# long-3_3v.net
KiCad netlist of a schematic drawn in EAGLE
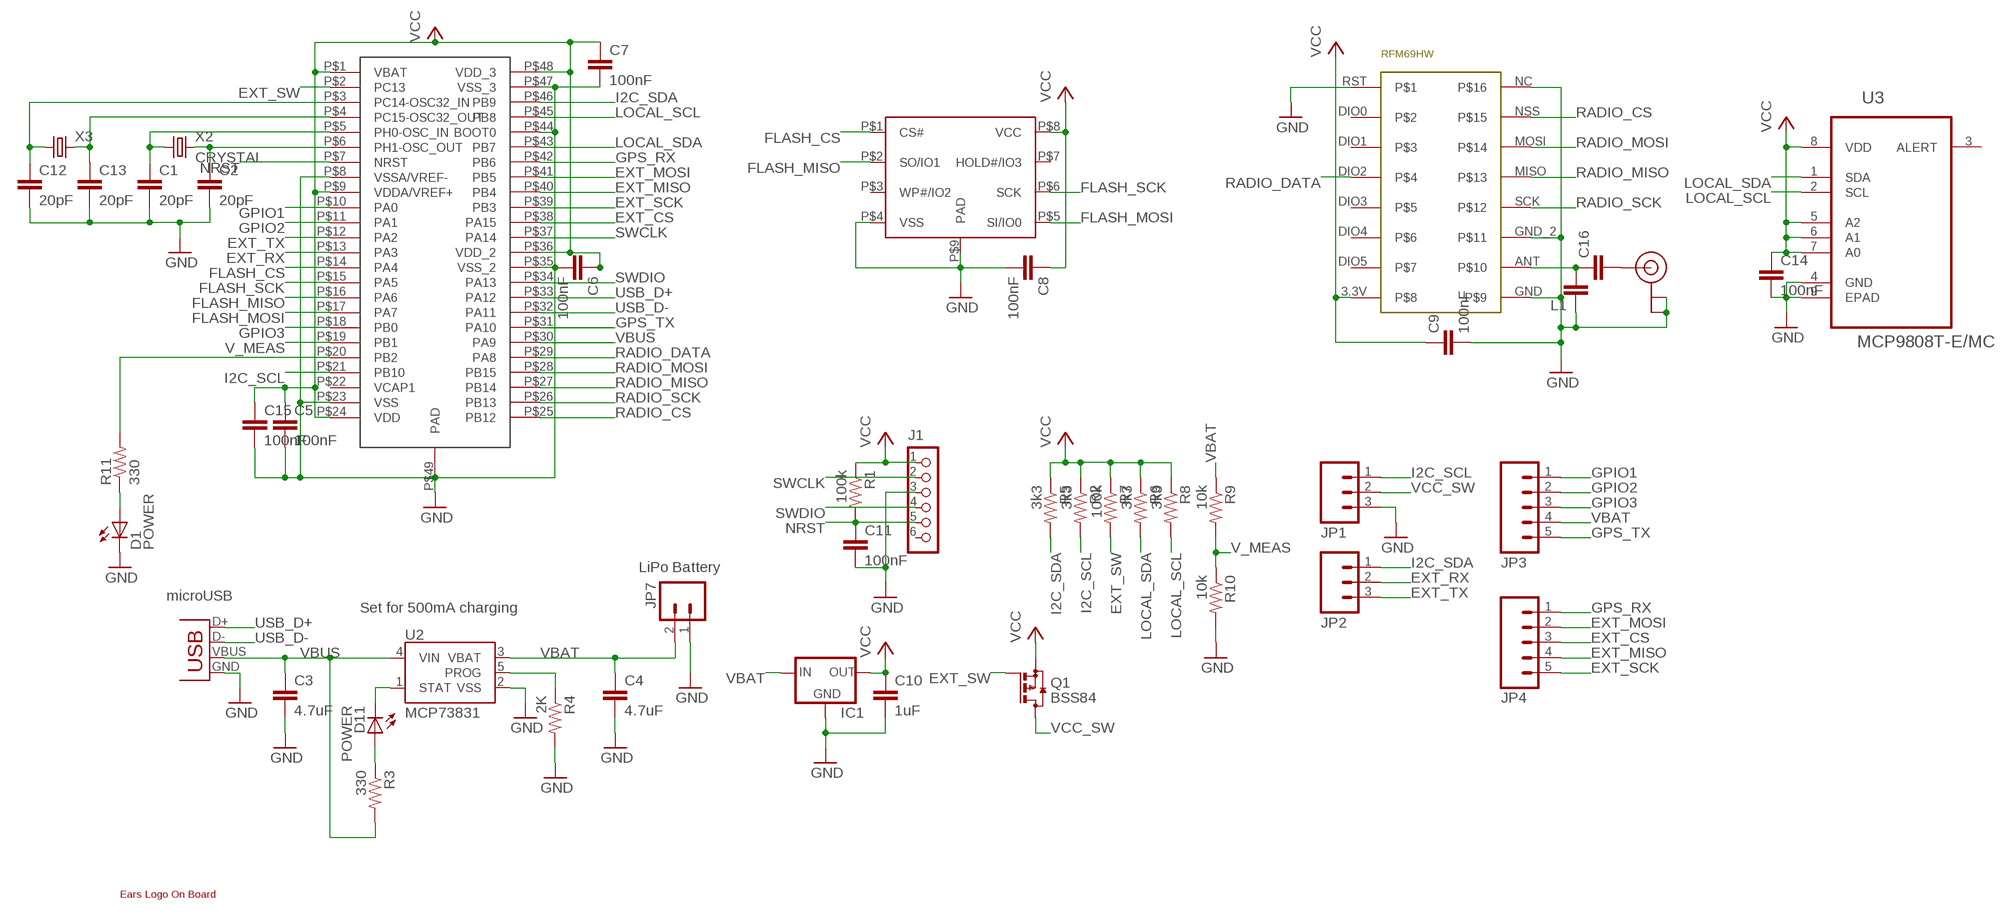
[diagram p0: schematic, sheet 1]

(export (version "E")
  (design (tool "Eeschema 10.0.6"))
  (components
    (comp (ref "C1")
      (value "20pF")
      (footprint "eagle-import:C0402")
      (libsource (lib "eagle-import") (part "C-EUC0402"))
    )
    (comp (ref "C2")
      (value "20pF")
      (footprint "eagle-import:C0402")
      (libsource (lib "eagle-import") (part "C-EUC0402"))
    )
    (comp (ref "C3")
      (value "4.7uF")
      (footprint "eagle-import:0402-CAP")
      (libsource (lib "eagle-import") (part "CAP0402-CAP"))
    )
    (comp (ref "C4")
      (value "4.7uF")
      (footprint "eagle-import:0402-CAP")
      (libsource (lib "eagle-import") (part "CAP0402-CAP"))
    )
    (comp (ref "C5")
      (value "100nF")
      (footprint "eagle-import:C0402")
      (libsource (lib "eagle-import") (part "C-EUC0402"))
    )
    (comp (ref "C6")
      (value "100nF")
      (footprint "eagle-import:C0402")
      (libsource (lib "eagle-import") (part "C-EUC0402"))
    )
    (comp (ref "C7")
      (value "100nF")
      (footprint "eagle-import:C0402")
      (libsource (lib "eagle-import") (part "C-EUC0402"))
    )
    (comp (ref "C8")
      (value "100nF")
      (footprint "eagle-import:C0402")
      (libsource (lib "eagle-import") (part "C-EUC0402"))
    )
    (comp (ref "C9")
      (value "100nF")
      (footprint "eagle-import:C0402")
      (libsource (lib "eagle-import") (part "C-EUC0402"))
    )
    (comp (ref "C10")
      (value "1uF")
      (footprint "eagle-import:C0402")
      (libsource (lib "eagle-import") (part "C-EUC0402"))
    )
    (comp (ref "C11")
      (value "100nF")
      (footprint "eagle-import:C0402")
      (libsource (lib "eagle-import") (part "C-EUC0402"))
    )
    (comp (ref "C12")
      (value "20pF")
      (footprint "eagle-import:C0402")
      (libsource (lib "eagle-import") (part "C-EUC0402"))
    )
    (comp (ref "C13")
      (value "20pF")
      (footprint "eagle-import:C0402")
      (libsource (lib "eagle-import") (part "C-EUC0402"))
    )
    (comp (ref "C14")
      (value "100nF")
      (footprint "eagle-import:C0402")
      (libsource (lib "eagle-import") (part "C-EUC0402"))
    )
    (comp (ref "C15")
      (value "100nF")
      (footprint "eagle-import:C0402")
      (libsource (lib "eagle-import") (part "C-EUC0402"))
    )
    (comp (ref "C16")
      (value "C-EUC0402")
      (footprint "eagle-import:C0402")
      (libsource (lib "eagle-import") (part "C-EUC0402"))
    )
    (comp (ref "D1")
      (value "POWER")
      (footprint "eagle-import:LED-0603")
      (libsource (lib "eagle-import") (part "LED0603"))
    )
    (comp (ref "D11")
      (value "POWER")
      (footprint "eagle-import:LED-0603")
      (libsource (lib "eagle-import") (part "LED0603"))
    )
    (comp (ref "IC1")
      (value "XC63FPM")
      (footprint "eagle-import:SOT23")
      (libsource (lib "eagle-import") (part "XC63FPM"))
    )
    (comp (ref "J1")
      (value "CON_HEADER_1X06-SMD-RIGHT-ANGLED")
      (footprint "eagle-import:M1X6_MALE_RIGHT_ANGLED_SMD")
      (libsource (lib "eagle-import") (part "CON_HEADER_1X06-SMD-RIGHT-ANGLED"))
    )
    (comp (ref "JP1")
      (value "M03PTH")
      (footprint "eagle-import:1X03")
      (libsource (lib "eagle-import") (part "M03PTH"))
    )
    (comp (ref "JP2")
      (value "M03PTH")
      (footprint "eagle-import:1X03")
      (libsource (lib "eagle-import") (part "M03PTH"))
    )
    (comp (ref "JP3")
      (value "M05PTH")
      (footprint "eagle-import:1X05")
      (libsource (lib "eagle-import") (part "M05PTH"))
    )
    (comp (ref "JP4")
      (value "M05PTH")
      (footprint "eagle-import:1X05")
      (libsource (lib "eagle-import") (part "M05PTH"))
    )
    (comp (ref "JP7")
      (value "LiPo Battery")
      (footprint "eagle-import:JST-2-SMD")
      (libsource (lib "eagle-import") (part "M02-JST-2MM-SMT"))
    )
    (comp (ref "L1")
      (value "C-EUC0402")
      (footprint "eagle-import:C0402")
      (libsource (lib "eagle-import") (part "C-EUC0402"))
    )
    (comp (ref "Q1")
      (value "BSS84")
      (footprint "eagle-import:SOT23")
      (libsource (lib "eagle-import") (part "BSS84"))
    )
    (comp (ref "R1")
      (value "100k")
      (footprint "eagle-import:0402-RES")
      (libsource (lib "eagle-import") (part "RESISTOR0402-RES"))
    )
    (comp (ref "R2")
      (value "3k3")
      (footprint "eagle-import:0402-RES")
      (libsource (lib "eagle-import") (part "RESISTOR0402-RES"))
    )
    (comp (ref "R3")
      (value "330")
      (footprint "eagle-import:0402-RES")
      (libsource (lib "eagle-import") (part "RESISTOR0402-RES"))
    )
    (comp (ref "R4")
      (value "2K")
      (footprint "eagle-import:0402-RES")
      (libsource (lib "eagle-import") (part "RESISTOR0402-RES"))
    )
    (comp (ref "R5")
      (value "3k3")
      (footprint "eagle-import:0402-RES")
      (libsource (lib "eagle-import") (part "RESISTOR0402-RES"))
    )
    (comp (ref "R6")
      (value "3k3")
      (footprint "eagle-import:0402-RES")
      (libsource (lib "eagle-import") (part "RESISTOR0402-RES"))
    )
    (comp (ref "R7")
      (value "100k")
      (footprint "eagle-import:0402-RES")
      (libsource (lib "eagle-import") (part "RESISTOR0402-RES"))
    )
    (comp (ref "R8")
      (value "3k3")
      (footprint "eagle-import:0402-RES")
      (libsource (lib "eagle-import") (part "RESISTOR0402-RES"))
    )
    (comp (ref "R9")
      (value "10k")
      (footprint "eagle-import:0402-RES")
      (libsource (lib "eagle-import") (part "RESISTOR0402-RES"))
    )
    (comp (ref "R10")
      (value "10k")
      (footprint "eagle-import:0402-RES")
      (libsource (lib "eagle-import") (part "RESISTOR0402-RES"))
    )
    (comp (ref "R11")
      (value "330")
      (footprint "eagle-import:0402-RES")
      (libsource (lib "eagle-import") (part "RESISTOR0402-RES"))
    )
    (comp (ref "U$1")
      (value "STM32F411CEU6")
      (footprint "eagle-import:STM32F411CEU6")
      (libsource (lib "eagle-import") (part "STM32F411CEU6"))
    )
    (comp (ref "U$2")
      (value "EARS-LOGO")
      (footprint "eagle-import:EARS-LOGO")
      (libsource (lib "eagle-import") (part "EARS-LOGO"))
    )
    (comp (ref "U$3")
      (value "RFM69HW")
      (footprint "eagle-import:RFM69HW")
      (libsource (lib "eagle-import") (part "RFM69HW"))
    )
    (comp (ref "U$4")
      (value "U.FL")
      (footprint "eagle-import:U.FL")
      (libsource (lib "eagle-import") (part "U.FL"))
    )
    (comp (ref "U$5")
      (value "S25FL256")
      (footprint "eagle-import:WSON-8")
      (libsource (lib "eagle-import") (part "S25FL256"))
    )
    (comp (ref "U2")
      (value "MCP73831")
      (footprint "eagle-import:SOT23-5")
      (libsource (lib "eagle-import") (part "MCP73831"))
    )
    (comp (ref "U3")
      (value "MCP9808T-E/MC")
      (footprint "eagle-import:DFN300X200X100-9N")
      (libsource (lib "eagle-import") (part "MCP9808T-E/MC"))
    )
    (comp (ref "X1")
      (value "Micro USB")
      (footprint "eagle-import:USB-MICROB")
      (libsource (lib "eagle-import") (part "USB-MICROB"))
    )
    (comp (ref "X2")
      (value "CRYSTAL")
      (footprint "eagle-import:ABRACON_ABM3_CRYSTAL")
      (libsource (lib "eagle-import") (part "ABRACON_ABM3_CRYSTAL"))
    )
    (comp (ref "X3")
      (value "CRYSTALS-NOGND-IQXC-25")
      (footprint "eagle-import:2.0X1.2-2PAD")
      (libsource (lib "eagle-import") (part "CRYSTALS-NOGND-IQXC-25"))
    )
  )
  (nets
    (net (code "1") (name "/EXT_CS") (class "Default")
      (node (ref "JP4") (pin "3") (pinfunction "3_3") (pintype "passive"))
      (node (ref "U$1") (pin "P$38") (pinfunction "PA15_P$38") (pintype "bidirectional"))
    )
    (net (code "2") (name "/EXT_MISO") (class "Default")
      (node (ref "JP4") (pin "4") (pinfunction "4_4") (pintype "passive"))
      (node (ref "U$1") (pin "P$40") (pinfunction "PB4_P$40") (pintype "bidirectional"))
    )
    (net (code "3") (name "/EXT_MOSI") (class "Default")
      (node (ref "JP4") (pin "2") (pinfunction "2_2") (pintype "passive"))
      (node (ref "U$1") (pin "P$41") (pinfunction "PB5_P$41") (pintype "bidirectional"))
    )
    (net (code "4") (name "/EXT_RX") (class "Default")
      (node (ref "JP2") (pin "2") (pinfunction "2_2") (pintype "passive"))
      (node (ref "U$1") (pin "P$13") (pinfunction "PA3_P$13") (pintype "bidirectional"))
    )
    (net (code "5") (name "/EXT_SCK") (class "Default")
      (node (ref "JP4") (pin "5") (pinfunction "5_5") (pintype "passive"))
      (node (ref "U$1") (pin "P$39") (pinfunction "PB3_P$39") (pintype "bidirectional"))
    )
    (net (code "6") (name "/EXT_SW") (class "Default")
      (node (ref "Q1") (pin "1") (pinfunction "G_1") (pintype "passive"))
      (node (ref "R7") (pin "2") (pinfunction "2_2") (pintype "passive"))
      (node (ref "U$1") (pin "P$2") (pinfunction "PC13_P$2") (pintype "bidirectional"))
    )
    (net (code "7") (name "/EXT_TX") (class "Default")
      (node (ref "JP2") (pin "3") (pinfunction "3_3") (pintype "passive"))
      (node (ref "U$1") (pin "P$12") (pinfunction "PA2_P$12") (pintype "bidirectional"))
    )
    (net (code "8") (name "/FLASH_CS") (class "Default")
      (node (ref "U$1") (pin "P$14") (pinfunction "PA4_P$14") (pintype "bidirectional"))
      (node (ref "U$5") (pin "P$1") (pinfunction "CS#_P$1") (pintype "bidirectional"))
    )
    (net (code "9") (name "/FLASH_MISO") (class "Default")
      (node (ref "U$1") (pin "P$16") (pinfunction "PA6_P$16") (pintype "bidirectional"))
      (node (ref "U$5") (pin "P$2") (pinfunction "SO/IO1_P$2") (pintype "bidirectional"))
    )
    (net (code "10") (name "/FLASH_MOSI") (class "Default")
      (node (ref "U$1") (pin "P$17") (pinfunction "PA7_P$17") (pintype "bidirectional"))
      (node (ref "U$5") (pin "P$5") (pinfunction "SI/IO0_P$5") (pintype "bidirectional"))
    )
    (net (code "11") (name "/FLASH_SCK") (class "Default")
      (node (ref "U$1") (pin "P$15") (pinfunction "PA5_P$15") (pintype "bidirectional"))
      (node (ref "U$5") (pin "P$6") (pinfunction "SCK_P$6") (pintype "bidirectional"))
    )
    (net (code "12") (name "/GPIO1") (class "Default")
      (node (ref "JP3") (pin "1") (pinfunction "1_1") (pintype "passive"))
      (node (ref "U$1") (pin "P$10") (pinfunction "PA0_P$10") (pintype "bidirectional"))
    )
    (net (code "13") (name "/GPIO2") (class "Default")
      (node (ref "JP3") (pin "2") (pinfunction "2_2") (pintype "passive"))
      (node (ref "U$1") (pin "P$11") (pinfunction "PA1_P$11") (pintype "bidirectional"))
    )
    (net (code "14") (name "/GPIO3") (class "Default")
      (node (ref "JP3") (pin "3") (pinfunction "3_3") (pintype "passive"))
      (node (ref "U$1") (pin "P$18") (pinfunction "PB0_P$18") (pintype "bidirectional"))
    )
    (net (code "15") (name "/GPS_RX") (class "Default")
      (node (ref "JP4") (pin "1") (pinfunction "1_1") (pintype "passive"))
      (node (ref "U$1") (pin "P$42") (pinfunction "PB6_P$42") (pintype "bidirectional"))
    )
    (net (code "16") (name "/GPS_TX") (class "Default")
      (node (ref "JP3") (pin "5") (pinfunction "5_5") (pintype "passive"))
      (node (ref "U$1") (pin "P$31") (pinfunction "PA10_P$31") (pintype "bidirectional"))
    )
    (net (code "17") (name "/I2C_SCL") (class "Default")
      (node (ref "JP1") (pin "1") (pinfunction "1_1") (pintype "passive"))
      (node (ref "R2") (pin "2") (pinfunction "2_2") (pintype "passive"))
      (node (ref "U$1") (pin "P$21") (pinfunction "PB10_P$21") (pintype "bidirectional"))
    )
    (net (code "18") (name "/I2C_SDA") (class "Default")
      (node (ref "JP2") (pin "1") (pinfunction "1_1") (pintype "passive"))
      (node (ref "R5") (pin "2") (pinfunction "2_2") (pintype "passive"))
      (node (ref "U$1") (pin "P$46") (pinfunction "PB9_P$46") (pintype "bidirectional"))
    )
    (net (code "19") (name "/LOCAL_SCL") (class "Default")
      (node (ref "R8") (pin "2") (pinfunction "2_2") (pintype "passive"))
      (node (ref "U$1") (pin "P$45") (pinfunction "PB8_P$45") (pintype "bidirectional"))
      (node (ref "U3") (pin "2") (pinfunction "SCL_2") (pintype "input"))
    )
    (net (code "20") (name "/LOCAL_SDA") (class "Default")
      (node (ref "R6") (pin "2") (pinfunction "2_2") (pintype "passive"))
      (node (ref "U$1") (pin "P$43") (pinfunction "PB7_P$43") (pintype "bidirectional"))
      (node (ref "U3") (pin "1") (pinfunction "SDA_1") (pintype "input"))
    )
    (net (code "21") (name "/NRST") (class "Default")
      (node (ref "C11") (pin "1") (pinfunction "1_1") (pintype "passive"))
      (node (ref "J1") (pin "5") (pinfunction "5_5") (pintype "passive"))
      (node (ref "R1") (pin "2") (pinfunction "2_2") (pintype "passive"))
      (node (ref "U$1") (pin "P$7") (pinfunction "NRST_P$7") (pintype "bidirectional"))
    )
    (net (code "22") (name "/RADIO_CS") (class "Default")
      (node (ref "U$1") (pin "P$25") (pinfunction "PB12_P$25") (pintype "bidirectional"))
      (node (ref "U$3") (pin "NSS") (pinfunction "P$15_NSS") (pintype "bidirectional"))
    )
    (net (code "23") (name "/RADIO_DATA") (class "Default")
      (node (ref "U$1") (pin "P$29") (pinfunction "PA8_P$29") (pintype "bidirectional"))
      (node (ref "U$3") (pin "DIO2") (pinfunction "P$4_DIO2") (pintype "bidirectional"))
    )
    (net (code "24") (name "/RADIO_MISO") (class "Default")
      (node (ref "U$1") (pin "P$27") (pinfunction "PB14_P$27") (pintype "bidirectional"))
      (node (ref "U$3") (pin "MISO") (pinfunction "P$13_MISO") (pintype "bidirectional"))
    )
    (net (code "25") (name "/RADIO_MOSI") (class "Default")
      (node (ref "U$1") (pin "P$28") (pinfunction "PB15_P$28") (pintype "bidirectional"))
      (node (ref "U$3") (pin "MOSI") (pinfunction "P$14_MOSI") (pintype "bidirectional"))
    )
    (net (code "26") (name "/RADIO_SCK") (class "Default")
      (node (ref "U$1") (pin "P$26") (pinfunction "PB13_P$26") (pintype "bidirectional"))
      (node (ref "U$3") (pin "SCK") (pinfunction "P$12_SCK") (pintype "bidirectional"))
    )
    (net (code "27") (name "/SWCLK") (class "Default")
      (node (ref "J1") (pin "2") (pinfunction "2_2") (pintype "bidirectional"))
      (node (ref "U$1") (pin "P$37") (pinfunction "PA14_P$37") (pintype "bidirectional"))
    )
    (net (code "28") (name "/SWDIO") (class "Default")
      (node (ref "J1") (pin "4") (pinfunction "4_4") (pintype "passive"))
      (node (ref "U$1") (pin "P$34") (pinfunction "PA13_P$34") (pintype "bidirectional"))
    )
    (net (code "29") (name "/USB_D+") (class "Default")
      (node (ref "U$1") (pin "P$33") (pinfunction "PA12_P$33") (pintype "bidirectional"))
      (node (ref "X1") (pin "D+") (pinfunction "D+_D+") (pintype "bidirectional"))
    )
    (net (code "30") (name "/USB_D-") (class "Default")
      (node (ref "U$1") (pin "P$32") (pinfunction "PA11_P$32") (pintype "bidirectional"))
      (node (ref "X1") (pin "D-") (pinfunction "D-_D-") (pintype "bidirectional"))
    )
    (net (code "31") (name "/VBAT") (class "Default")
      (node (ref "C4") (pin "1") (pinfunction "1_1") (pintype "passive"))
      (node (ref "IC1") (pin "3") (pinfunction "IN_3") (pintype "input"))
      (node (ref "JP3") (pin "4") (pinfunction "4_4") (pintype "passive"))
      (node (ref "JP7") (pin "2") (pinfunction "2_2") (pintype "passive"))
      (node (ref "R9") (pin "1") (pinfunction "1_1") (pintype "passive"))
      (node (ref "U2") (pin "3") (pinfunction "VBAT_3") (pintype "power_in"))
    )
    (net (code "32") (name "/VBUS") (class "Default")
      (node (ref "C3") (pin "1") (pinfunction "1_1") (pintype "passive"))
      (node (ref "R3") (pin "2") (pinfunction "2_2") (pintype "passive"))
      (node (ref "U$1") (pin "P$30") (pinfunction "PA9_P$30") (pintype "bidirectional"))
      (node (ref "U2") (pin "4") (pinfunction "VIN_4") (pintype "power_in"))
      (node (ref "X1") (pin "VBUS") (pinfunction "VBUS_VBUS") (pintype "bidirectional"))
    )
    (net (code "33") (name "/VCC_SW") (class "Default")
      (node (ref "JP1") (pin "2") (pinfunction "2_2") (pintype "passive"))
      (node (ref "Q1") (pin "3") (pinfunction "D_3") (pintype "passive"))
    )
    (net (code "34") (name "/V_MEAS") (class "Default")
      (node (ref "R10") (pin "1") (pinfunction "1_1") (pintype "passive"))
      (node (ref "R9") (pin "2") (pinfunction "2_2") (pintype "passive"))
      (node (ref "U$1") (pin "P$19") (pinfunction "PB1_P$19") (pintype "bidirectional"))
    )
    (net (code "35") (name "GND") (class "Default")
      (node (ref "C1") (pin "2") (pinfunction "2_2") (pintype "passive"))
      (node (ref "C10") (pin "2") (pinfunction "2_2") (pintype "passive"))
      (node (ref "C11") (pin "2") (pinfunction "2_2") (pintype "passive"))
      (node (ref "C12") (pin "2") (pinfunction "2_2") (pintype "passive"))
      (node (ref "C13") (pin "2") (pinfunction "2_2") (pintype "passive"))
      (node (ref "C14") (pin "2") (pinfunction "2_2") (pintype "passive"))
      (node (ref "C15") (pin "2") (pinfunction "2_2") (pintype "passive"))
      (node (ref "C2") (pin "2") (pinfunction "2_2") (pintype "passive"))
      (node (ref "C3") (pin "2") (pinfunction "2_2") (pintype "passive"))
      (node (ref "C4") (pin "2") (pinfunction "2_2") (pintype "passive"))
      (node (ref "C5") (pin "2") (pinfunction "2_2") (pintype "passive"))
      (node (ref "C6") (pin "2") (pinfunction "2_2") (pintype "passive"))
      (node (ref "C7") (pin "2") (pinfunction "2_2") (pintype "passive"))
      (node (ref "C8") (pin "2") (pinfunction "2_2") (pintype "passive"))
      (node (ref "C9") (pin "2") (pinfunction "2_2") (pintype "passive"))
      (node (ref "D1") (pin "C") (pinfunction "C_C") (pintype "passive"))
      (node (ref "IC1") (pin "1") (pinfunction "GND_1") (pintype "input"))
      (node (ref "J1") (pin "3") (pinfunction "3_3") (pintype "passive"))
      (node (ref "JP1") (pin "3") (pinfunction "3_3") (pintype "passive"))
      (node (ref "JP7") (pin "1") (pinfunction "1_1") (pintype "passive"))
      (node (ref "L1") (pin "1") (pinfunction "1_1") (pintype "passive"))
      (node (ref "R10") (pin "2") (pinfunction "2_2") (pintype "passive"))
      (node (ref "R4") (pin "2") (pinfunction "2_2") (pintype "passive"))
      (node (ref "U$1") (pin "P$23") (pinfunction "VSS_P$23") (pintype "bidirectional"))
      (node (ref "U$1") (pin "P$35") (pinfunction "VSS_2_P$35") (pintype "bidirectional"))
      (node (ref "U$1") (pin "P$44") (pinfunction "BOOT0_P$44") (pintype "bidirectional"))
      (node (ref "U$1") (pin "P$47") (pinfunction "VSS_3_P$47") (pintype "bidirectional"))
      (node (ref "U$1") (pin "P$49") (pinfunction "PAD_P$49") (pintype "bidirectional"))
      (node (ref "U$1") (pin "P$8") (pinfunction "VSSA/VREF-_P$8") (pintype "bidirectional"))
      (node (ref "U$3") (pin "GND") (pinfunction "P$9_GND") (pintype "bidirectional"))
      (node (ref "U$3") (pin "GND_2") (pinfunction "P$11_GND_2") (pintype "bidirectional"))
      (node (ref "U$3") (pin "NC") (pinfunction "P$16_NC") (pintype "bidirectional"))
      (node (ref "U$3") (pin "RST") (pinfunction "P$1_RST") (pintype "bidirectional"))
      (node (ref "U$4") (pin "P$1") (pinfunction "GND_P$1") (pintype "bidirectional"))
      (node (ref "U$4") (pin "P$2") (pinfunction "GND_P$2") (pintype "bidirectional"))
      (node (ref "U$5") (pin "P$4") (pinfunction "VSS_P$4") (pintype "bidirectional"))
      (node (ref "U$5") (pin "P$9") (pinfunction "PAD_P$9") (pintype "bidirectional"))
      (node (ref "U2") (pin "2") (pinfunction "VSS_2") (pintype "power_in"))
      (node (ref "U3") (pin "4") (pinfunction "GND_4") (pintype "power_in"))
      (node (ref "U3") (pin "9") (pinfunction "EPAD_9") (pintype "passive"))
      (node (ref "X1") (pin "GND") (pinfunction "GND_GND") (pintype "bidirectional"))
    )
    (net (code "36") (name "Net-(D1-PadA)") (class "Default")
      (node (ref "D1") (pin "A") (pinfunction "A_A") (pintype "passive"))
      (node (ref "R11") (pin "1") (pinfunction "1_1") (pintype "passive"))
    )
    (net (code "37") (name "Net-(D11-PadA)") (class "Default")
      (node (ref "D11") (pin "A") (pinfunction "A_A") (pintype "passive"))
      (node (ref "R3") (pin "1") (pinfunction "1_1") (pintype "passive"))
    )
    (net (code "38") (name "Net-(U$1-PB2)") (class "Default")
      (node (ref "R11") (pin "2") (pinfunction "2_2") (pintype "passive"))
      (node (ref "U$1") (pin "P$20") (pinfunction "PB2_P$20") (pintype "bidirectional"))
    )
    (net (code "39") (name "Net-(U$1-PC14-OSC32_IN)") (class "Default")
      (node (ref "C12") (pin "1") (pinfunction "1_1") (pintype "passive"))
      (node (ref "U$1") (pin "P$3") (pinfunction "PC14-OSC32_IN_P$3") (pintype "bidirectional"))
      (node (ref "X3") (pin "1") (pinfunction "1_1") (pintype "passive"))
    )
    (net (code "40") (name "Net-(U$1-PC15-OSC32_OUT)") (class "Default")
      (node (ref "C13") (pin "1") (pinfunction "1_1") (pintype "passive"))
      (node (ref "U$1") (pin "P$4") (pinfunction "PC15-OSC32_OUT_P$4") (pintype "bidirectional"))
      (node (ref "X3") (pin "2") (pinfunction "2_2") (pintype "passive"))
    )
    (net (code "41") (name "Net-(U$1-PH0-OSC_IN)") (class "Default")
      (node (ref "C1") (pin "1") (pinfunction "1_1") (pintype "passive"))
      (node (ref "U$1") (pin "P$5") (pinfunction "PH0-OSC_IN_P$5") (pintype "bidirectional"))
      (node (ref "X2") (pin "P$1") (pinfunction "1_P$1") (pintype "passive"))
    )
    (net (code "42") (name "Net-(U$1-PH1-OSC_OUT)") (class "Default")
      (node (ref "C2") (pin "1") (pinfunction "1_1") (pintype "passive"))
      (node (ref "U$1") (pin "P$6") (pinfunction "PH1-OSC_OUT_P$6") (pintype "bidirectional"))
      (node (ref "X2") (pin "P$2") (pinfunction "2_P$2") (pintype "passive"))
    )
    (net (code "43") (name "Net-(U$3-P$10)") (class "Default")
      (node (ref "C16") (pin "1") (pinfunction "1_1") (pintype "passive"))
      (node (ref "L1") (pin "2") (pinfunction "2_2") (pintype "passive"))
      (node (ref "U$3") (pin "ANT") (pinfunction "P$10_ANT") (pintype "bidirectional"))
    )
    (net (code "44") (name "Net-(U$4-SIGNAL)") (class "Default")
      (node (ref "C16") (pin "2") (pinfunction "2_2") (pintype "passive"))
      (node (ref "U$4") (pin "P$3") (pinfunction "SIGNAL_P$3") (pintype "bidirectional"))
    )
    (net (code "45") (name "Net-(U2-PROG)") (class "Default")
      (node (ref "R4") (pin "1") (pinfunction "1_1") (pintype "passive"))
      (node (ref "U2") (pin "5") (pinfunction "PROG_5") (pintype "input"))
    )
    (net (code "46") (name "Net-(U2-STAT)") (class "Default")
      (node (ref "D11") (pin "C") (pinfunction "C_C") (pintype "passive"))
      (node (ref "U2") (pin "1") (pinfunction "STAT_1") (pintype "output"))
    )
    (net (code "47") (name "VCC") (class "Default")
      (node (ref "C10") (pin "1") (pinfunction "1_1") (pintype "passive"))
      (node (ref "C14") (pin "1") (pinfunction "1_1") (pintype "passive"))
      (node (ref "C15") (pin "1") (pinfunction "1_1") (pintype "passive"))
      (node (ref "C5") (pin "1") (pinfunction "1_1") (pintype "passive"))
      (node (ref "C6") (pin "1") (pinfunction "1_1") (pintype "passive"))
      (node (ref "C7") (pin "1") (pinfunction "1_1") (pintype "passive"))
      (node (ref "C8") (pin "1") (pinfunction "1_1") (pintype "passive"))
      (node (ref "C9") (pin "1") (pinfunction "1_1") (pintype "passive"))
      (node (ref "IC1") (pin "2") (pinfunction "OUT_2") (pintype "passive"))
      (node (ref "J1") (pin "1") (pinfunction "1_1") (pintype "bidirectional"))
      (node (ref "Q1") (pin "2") (pinfunction "S_2") (pintype "passive"))
      (node (ref "R1") (pin "1") (pinfunction "1_1") (pintype "passive"))
      (node (ref "R2") (pin "1") (pinfunction "1_1") (pintype "passive"))
      (node (ref "R5") (pin "1") (pinfunction "1_1") (pintype "passive"))
      (node (ref "R6") (pin "1") (pinfunction "1_1") (pintype "passive"))
      (node (ref "R7") (pin "1") (pinfunction "1_1") (pintype "passive"))
      (node (ref "R8") (pin "1") (pinfunction "1_1") (pintype "passive"))
      (node (ref "U$1") (pin "P$1") (pinfunction "VBAT_P$1") (pintype "bidirectional"))
      (node (ref "U$1") (pin "P$24") (pinfunction "VDD_P$24") (pintype "bidirectional"))
      (node (ref "U$1") (pin "P$36") (pinfunction "VDD_2_P$36") (pintype "bidirectional"))
      (node (ref "U$1") (pin "P$48") (pinfunction "VDD_3_P$48") (pintype "bidirectional"))
      (node (ref "U$1") (pin "P$9") (pinfunction "VDDA/VREF+_P$9") (pintype "bidirectional"))
      (node (ref "U$3") (pin "3.3V") (pinfunction "P$8_3.3V") (pintype "bidirectional"))
      (node (ref "U$5") (pin "P$8") (pinfunction "VCC_P$8") (pintype "bidirectional"))
      (node (ref "U3") (pin "5") (pinfunction "A2_5") (pintype "input"))
      (node (ref "U3") (pin "6") (pinfunction "A1_6") (pintype "input"))
      (node (ref "U3") (pin "7") (pinfunction "A0_7") (pintype "input"))
      (node (ref "U3") (pin "8") (pinfunction "VDD_8") (pintype "power_in"))
    )
    (net (code "48") (name "unconnected-(J1-Pad6)") (class "Default")
      (node (ref "J1") (pin "6") (pinfunction "6_6") (pintype "passive"))
    )
    (net (code "49") (name "unconnected-(U$1-VCAP1-PadP$22)") (class "Default")
      (node (ref "U$1") (pin "P$22") (pinfunction "VCAP1_P$22") (pintype "bidirectional"))
    )
    (net (code "50") (name "unconnected-(U$3-P$2-PadDIO0)") (class "Default")
      (node (ref "U$3") (pin "DIO0") (pinfunction "P$2_DIO0") (pintype "bidirectional"))
    )
    (net (code "51") (name "unconnected-(U$3-P$3-PadDIO1)") (class "Default")
      (node (ref "U$3") (pin "DIO1") (pinfunction "P$3_DIO1") (pintype "bidirectional"))
    )
    (net (code "52") (name "unconnected-(U$3-P$5-PadDIO3)") (class "Default")
      (node (ref "U$3") (pin "DIO3") (pinfunction "P$5_DIO3") (pintype "bidirectional"))
    )
    (net (code "53") (name "unconnected-(U$3-P$6-PadDIO4)") (class "Default")
      (node (ref "U$3") (pin "DIO4") (pinfunction "P$6_DIO4") (pintype "bidirectional"))
    )
    (net (code "54") (name "unconnected-(U$3-P$7-PadDIO5)") (class "Default")
      (node (ref "U$3") (pin "DIO5") (pinfunction "P$7_DIO5") (pintype "bidirectional"))
    )
    (net (code "55") (name "unconnected-(U$5-HOLD#{slash}IO3-PadP$7)") (class "Default")
      (node (ref "U$5") (pin "P$7") (pinfunction "HOLD#/IO3_P$7") (pintype "bidirectional"))
    )
    (net (code "56") (name "unconnected-(U$5-WP#{slash}IO2-PadP$3)") (class "Default")
      (node (ref "U$5") (pin "P$3") (pinfunction "WP#/IO2_P$3") (pintype "bidirectional"))
    )
    (net (code "57") (name "unconnected-(U3-ALERT-Pad3)") (class "Default")
      (node (ref "U3") (pin "3") (pinfunction "ALERT_3") (pintype "output"))
    )
  )
)
